# ATmega128RFA1-DevBoard.net
KiCad netlist of a schematic drawn in EAGLE
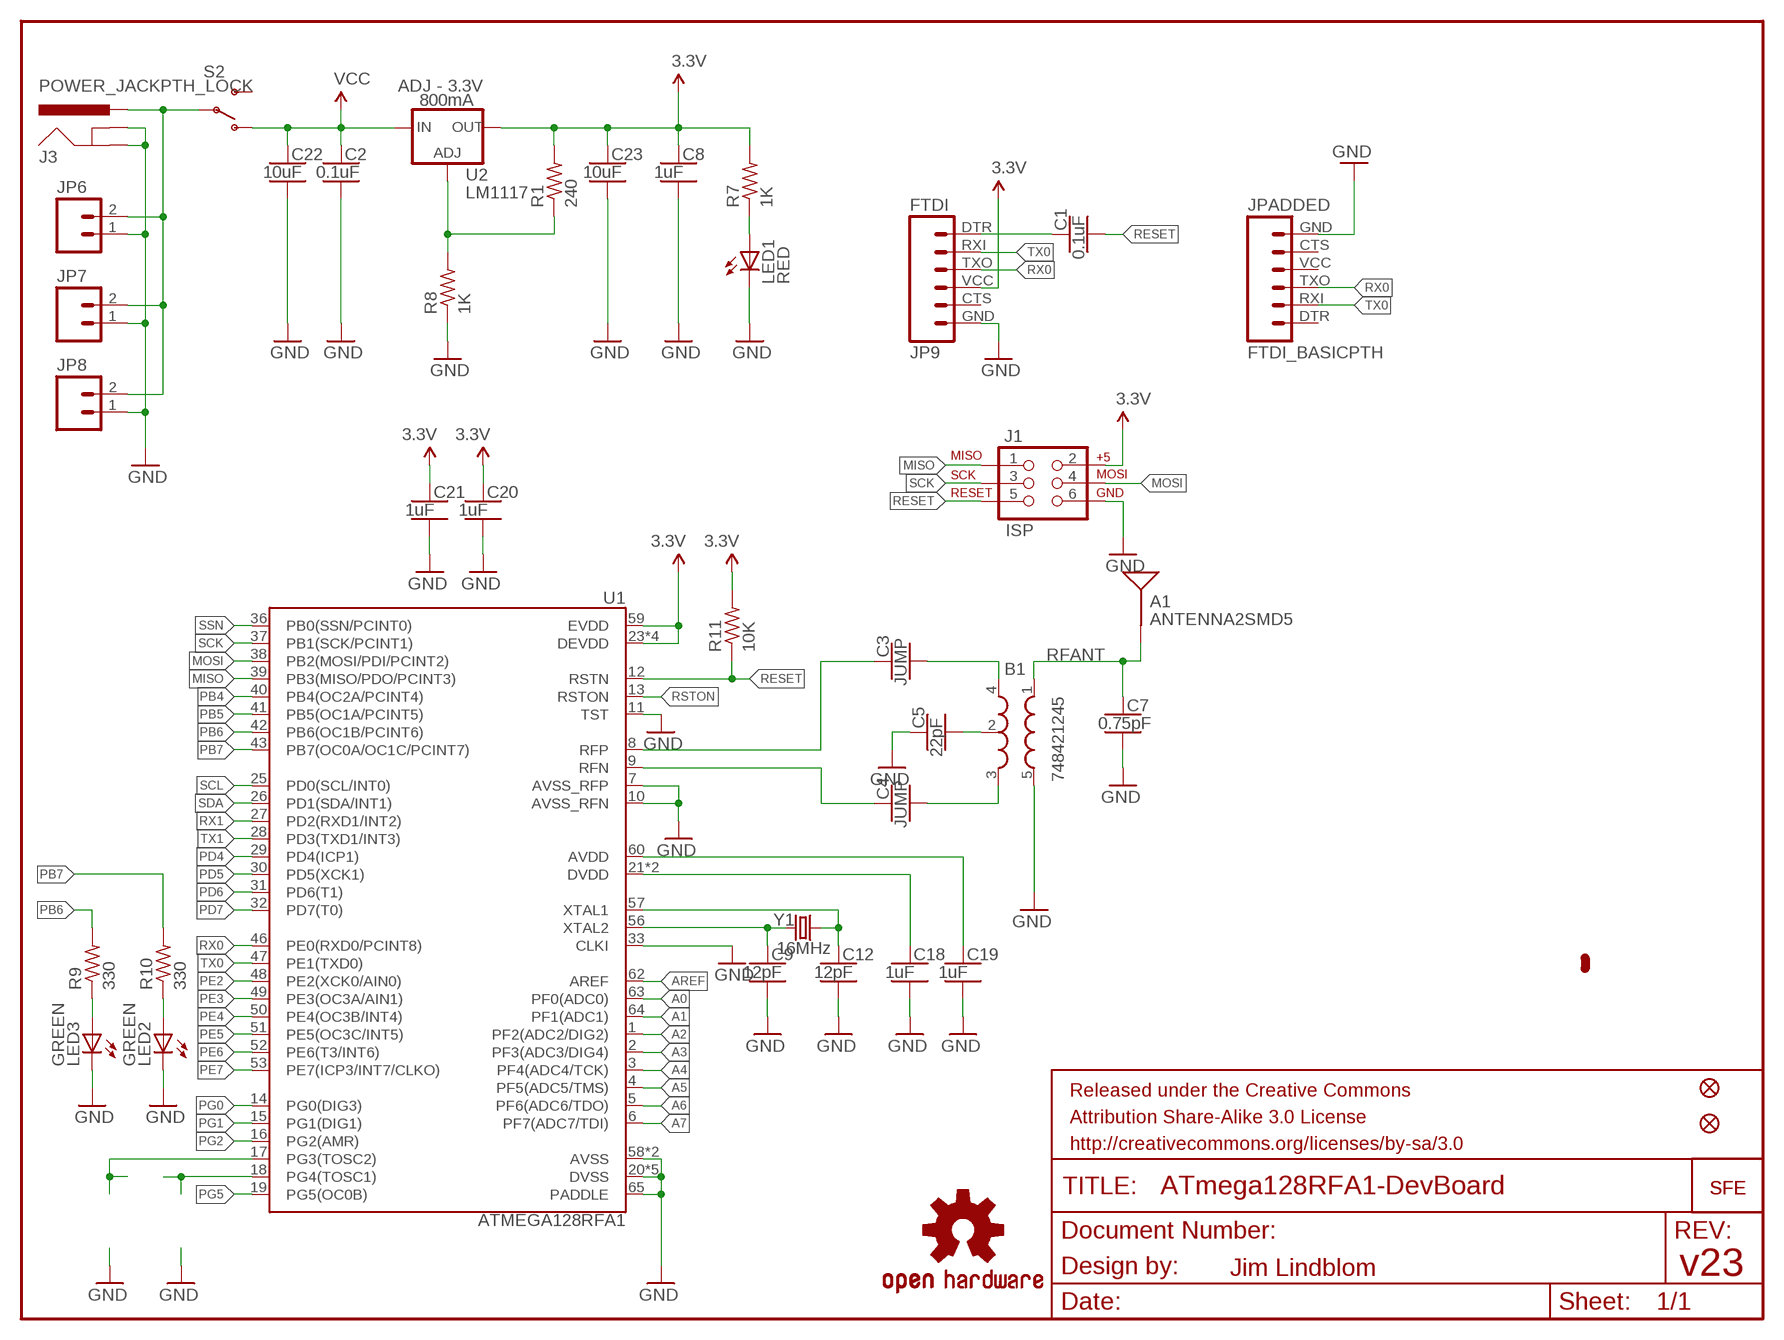
[diagram p0: schematic, sheet 1]

(export (version "E")
  (design (tool "Eeschema 10.0.6"))
  (components
    (comp (ref "A1")
      (value "ANTENNA2SMD5")
      (footprint "eagle-import:ANTENNA-CHIP5")
      (libsource (lib "eagle-import") (part "ANTENNA2SMD5"))
    )
    (comp (ref "B1")
      (value "748421245")
      (footprint "eagle-import:BALUN")
      (libsource (lib "eagle-import") (part "BALUN0805"))
    )
    (comp (ref "C1")
      (value "0.1uF")
      (footprint "eagle-import:CAPC2012X140_HS")
      (fields
        (field (name "MFR") "Murata Electronics North America")
        (field (name "MPN") "GRM21BR71H104KA01L")
      )
      (libsource (lib "eagle-import") (part "CAPACITOR-NP_SMD-2012-0805_CERAMIC-0.1UF"))
    )
    (comp (ref "C2")
      (value "0.1uF")
      (footprint "eagle-import:CAPC2012X140_HS")
      (fields
        (field (name "MFR") "Murata Electronics North America")
        (field (name "MPN") "GRM21BR71H104KA01L")
      )
      (libsource (lib "eagle-import") (part "CAPACITOR-NP_SMD-2012-0805_CERAMIC-0.1UF"))
    )
    (comp (ref "C3")
      (value "JUMP")
      (footprint "eagle-import:CAPC2012X140_HS")
      (libsource (lib "eagle-import") (part "CAPACITOR-NP_SMD-2012-0805_CERAMIC"))
    )
    (comp (ref "C4")
      (value "JUMP")
      (footprint "eagle-import:CAPC2012X140_HS")
      (libsource (lib "eagle-import") (part "CAPACITOR-NP_SMD-2012-0805_CERAMIC"))
    )
    (comp (ref "C5")
      (value "22pF")
      (footprint "eagle-import:CAPC2012X140_HS")
      (fields
        (field (name "MFR") "Murata Electronics North America")
        (field (name "MPN") "GRM21A5C2E220JW01D")
      )
      (libsource (lib "eagle-import") (part "CAPACITOR-NP_SMD-2012-0805_CERAMIC-22PF"))
    )
    (comp (ref "C7")
      (value "0.75pF")
      (footprint "eagle-import:CAPC2012X140_HS")
      (fields
        (field (name "MFR") "Murata Electronics North America")
        (field (name "MPN") "GQM2195C2AR75CB01D")
      )
      (libsource (lib "eagle-import") (part "CAPACITOR-NP_SMD-2012-0805_CERAMIC-0.75PF"))
    )
    (comp (ref "C8")
      (value "1uF")
      (footprint "eagle-import:CAPC2012X140_HS")
      (fields
        (field (name "MFR") "Murata Electronics North America")
        (field (name "MPN") "GRM21BR71H105KA12L")
      )
      (libsource (lib "eagle-import") (part "CAPACITOR-NP_SMD-2012-0805_CERAMIC-1UF"))
    )
    (comp (ref "C9")
      (value "12pF")
      (footprint "eagle-import:CAPC2012X140_HS")
      (fields
        (field (name "MFR") "Murata Electronics North America")
        (field (name "MPN") "GRM21A5C2E120JW01D")
      )
      (libsource (lib "eagle-import") (part "CAPACITOR-NP_SMD-2012-0805_CERAMIC-12PF"))
    )
    (comp (ref "C12")
      (value "12pF")
      (footprint "eagle-import:CAPC2012X140_HS")
      (fields
        (field (name "MFR") "Murata Electronics North America")
        (field (name "MPN") "GRM21A5C2E120JW01D")
      )
      (libsource (lib "eagle-import") (part "CAPACITOR-NP_SMD-2012-0805_CERAMIC-12PF"))
    )
    (comp (ref "C18")
      (value "1uF")
      (footprint "eagle-import:CAPC2012X140_HS")
      (fields
        (field (name "MFR") "Murata Electronics North America")
        (field (name "MPN") "GRM21BR71H105KA12L")
      )
      (libsource (lib "eagle-import") (part "CAPACITOR-NP_SMD-2012-0805_CERAMIC-1UF"))
    )
    (comp (ref "C19")
      (value "1uF")
      (footprint "eagle-import:CAPC2012X140_HS")
      (fields
        (field (name "MFR") "Murata Electronics North America")
        (field (name "MPN") "GRM21BR71H105KA12L")
      )
      (libsource (lib "eagle-import") (part "CAPACITOR-NP_SMD-2012-0805_CERAMIC-1UF"))
    )
    (comp (ref "C20")
      (value "1uF")
      (footprint "eagle-import:CAPC2012X140_HS")
      (fields
        (field (name "MFR") "Murata Electronics North America")
        (field (name "MPN") "GRM21BR71H105KA12L")
      )
      (libsource (lib "eagle-import") (part "CAPACITOR-NP_SMD-2012-0805_CERAMIC-1UF"))
    )
    (comp (ref "C21")
      (value "1uF")
      (footprint "eagle-import:CAPC2012X140_HS")
      (fields
        (field (name "MFR") "Murata Electronics North America")
        (field (name "MPN") "GRM21BR71H105KA12L")
      )
      (libsource (lib "eagle-import") (part "CAPACITOR-NP_SMD-2012-0805_CERAMIC-1UF"))
    )
    (comp (ref "C22")
      (value "10uF")
      (footprint "eagle-import:CAPC2012X140_HS")
      (fields
        (field (name "MFR") "Murata Electronics North America")
        (field (name "MPN") "GRM21BR61E106KA73L")
      )
      (libsource (lib "eagle-import") (part "CAPACITOR-NP_SMD-2012-0805_CERAMIC-10UF"))
    )
    (comp (ref "C23")
      (value "10uF")
      (footprint "eagle-import:CAPC2012X140_HS")
      (fields
        (field (name "MFR") "Murata Electronics North America")
        (field (name "MPN") "GRM21BR61E106KA73L")
      )
      (libsource (lib "eagle-import") (part "CAPACITOR-NP_SMD-2012-0805_CERAMIC-10UF"))
    )
    (comp (ref "FID1")
      (value "FIDUCIALUFIDUCIAL")
      (footprint "eagle-import:MICRO-FIDUCIAL")
      (libsource (lib "eagle-import") (part "FIDUCIALUFIDUCIAL"))
    )
    (comp (ref "FID2")
      (value "FIDUCIALUFIDUCIAL")
      (footprint "eagle-import:MICRO-FIDUCIAL")
      (libsource (lib "eagle-import") (part "FIDUCIALUFIDUCIAL"))
    )
    (comp (ref "J1")
      (value "ISP")
      (footprint "eagle-import:2X3-NS")
      (libsource (lib "eagle-import") (part "AVR_SPI_PRG_6NS"))
    )
    (comp (ref "J3")
      (value "POWER_JACKPTH_LOCK")
      (footprint "eagle-import:POWER_JACK_PTH_LOCK")
      (libsource (lib "eagle-import") (part "POWER_JACKPTH_LOCK"))
    )
    (comp (ref "JP4")
      (value "LOGO-SFENEW")
      (footprint "eagle-import:SFE-NEW-WEBLOGO")
      (libsource (lib "eagle-import") (part "LOGO-SFENEW"))
    )
    (comp (ref "JP6")
      (value "M02JST-PTH-2")
      (footprint "eagle-import:JST-2-PTH")
      (libsource (lib "eagle-import") (part "M02JST-PTH-2"))
    )
    (comp (ref "JP7")
      (value "M021X02_NO_SILK")
      (footprint "eagle-import:1X02_NO_SILK")
      (libsource (lib "eagle-import") (part "M021X02_NO_SILK"))
    )
    (comp (ref "JP8")
      (value "M023.5MM-NO_SILK")
      (footprint "eagle-import:SCREWTERMINAL-3.5MM-2-NS")
      (libsource (lib "eagle-import") (part "M023.5MM-NO_SILK"))
    )
    (comp (ref "JP9")
      (value "FTDI")
      (footprint "eagle-import:FTDI_BASIC")
      (libsource (lib "eagle-import") (part "FTDI_BASICPTH"))
    )
    (comp (ref "JP10")
      (value "LOGO-SFENEW")
      (footprint "eagle-import:SFE-NEW-WEBLOGO")
      (libsource (lib "eagle-import") (part "LOGO-SFENEW"))
    )
    (comp (ref "JPADDED")
      (value "FTDI_BASICPTH")
      (footprint "eagle-import:FTDI_BASIC")
      (fields (field (name "MFR") "Amphenol FCI") (field (name "MPN") "68016-406HLF"))
      (libsource (lib "eagle-import") (part "quadparts_prebuilt_FTDI_BASICPTH"))
    )
    (comp (ref "LED1")
      (value "RED")
      (footprint "eagle-import:LED-0603")
      (libsource (lib "eagle-import") (part "LED0603"))
    )
    (comp (ref "LED2")
      (value "GREEN")
      (footprint "eagle-import:LED-0603")
      (libsource (lib "eagle-import") (part "LED0603"))
    )
    (comp (ref "LED3")
      (value "GREEN")
      (footprint "eagle-import:LED-0603")
      (libsource (lib "eagle-import") (part "LED0603"))
    )
    (comp (ref "R1")
      (value "240")
      (footprint "eagle-import:RESC2012X60_HS")
      (libsource (lib "eagle-import") (part "RESISTOR_SMD-2012-0805"))
    )
    (comp (ref "R7")
      (value "1K")
      (footprint "eagle-import:RESC2012X60_HS")
      (libsource (lib "eagle-import") (part "RESISTOR_SMD-2012-0805"))
    )
    (comp (ref "R8")
      (value "1K")
      (footprint "eagle-import:RESC2012X60_HS")
      (libsource (lib "eagle-import") (part "RESISTOR_SMD-2012-0805"))
    )
    (comp (ref "R9")
      (value "330")
      (footprint "eagle-import:RESC2012X60_HS")
      (fields (field (name "MFR") "Yageo") (field (name "MPN") "RC0805JR-07330RL"))
      (libsource (lib "eagle-import") (part "RESISTOR_SMD-2012-0805-330"))
    )
    (comp (ref "R10")
      (value "330")
      (footprint "eagle-import:RESC2012X60_HS")
      (fields (field (name "MFR") "Yageo") (field (name "MPN") "RC0805JR-07330RL"))
      (libsource (lib "eagle-import") (part "RESISTOR_SMD-2012-0805-330"))
    )
    (comp (ref "R11")
      (value "10K")
      (footprint "eagle-import:RESC2012X60_HS")
      (fields (field (name "MFR") "Yageo") (field (name "MPN") "RC0805JR-0710KL"))
      (libsource (lib "eagle-import") (part "RESISTOR_SMD-2012-0805-10K"))
    )
    (comp (ref "S2")
      (value "SWITCH-SPST-SMD-A")
      (footprint "eagle-import:SWITCH-SPST-SMD-A")
      (libsource (lib "eagle-import") (part "SWITCH-SPST-SMD-A"))
    )
    (comp (ref "U$1")
      (value "OSHW-LOGOS")
      (footprint "eagle-import:OSHW-LOGO-S")
      (libsource (lib "eagle-import") (part "OSHW-LOGOS"))
    )
    (comp (ref "U1")
      (value "ATMEGA128RFA1")
      (footprint "eagle-import:QFN-64")
      (libsource (lib "eagle-import") (part "ATMEGA128RFA1"))
    )
    (comp (ref "U2")
      (value "LM1117")
      (footprint "eagle-import:SOT223")
      (libsource (lib "eagle-import") (part "V_REG_317SMD"))
    )
    (comp (ref "Y1")
      (value "16MHz")
      (footprint "eagle-import:CRYSTAL-SMD-5X3")
      (libsource (lib "eagle-import") (part "CRYSTAL5X3"))
    )
  )
  (nets
    (net (code "1") (name "/RFANT") (class "Default")
      (node (ref "A1") (pin "FEED") (pinfunction "SIGNAL_FEED") (pintype "bidirectional"))
      (node (ref "B1") (pin "1") (pinfunction "IN_1") (pintype "bidirectional"))
      (node (ref "C7") (pin "1") (pinfunction "1_1") (pintype "passive"))
    )
    (net (code "2") (name "3.3V") (class "Default")
      (node (ref "C20") (pin "1") (pinfunction "1_1") (pintype "passive"))
      (node (ref "C21") (pin "1") (pinfunction "1_1") (pintype "passive"))
      (node (ref "C23") (pin "1") (pinfunction "1_1") (pintype "passive"))
      (node (ref "C8") (pin "1") (pinfunction "1_1") (pintype "passive"))
      (node (ref "J1") (pin "2") (pinfunction "2_2") (pintype "passive"))
      (node (ref "JP9") (pin "VCC") (pinfunction "4_VCC") (pintype "passive"))
      (node (ref "R1") (pin "2") (pinfunction "2_2") (pintype "passive"))
      (node (ref "R11") (pin "2") (pinfunction "2_2") (pintype "passive"))
      (node (ref "R7") (pin "2") (pinfunction "2_2") (pintype "passive"))
      (node (ref "U1") (pin "23") (pinfunction "DEVDD_23") (pintype "bidirectional"))
      (node (ref "U1") (pin "34") (pinfunction "DEVDD_34") (pintype "bidirectional"))
      (node (ref "U1") (pin "44") (pinfunction "DEVDD_44") (pintype "bidirectional"))
      (node (ref "U1") (pin "54") (pinfunction "DEVDD_54") (pintype "bidirectional"))
      (node (ref "U1") (pin "59") (pinfunction "EVDD_59") (pintype "bidirectional"))
      (node (ref "U2") (pin "2") (pinfunction "OUT_2") (pintype "output"))
    )
    (net (code "3") (name "A0") (class "Default")
      (node (ref "U1") (pin "63") (pinfunction "PF0(ADC0)_63") (pintype "bidirectional"))
    )
    (net (code "4") (name "A1") (class "Default")
      (node (ref "U1") (pin "64") (pinfunction "PF1(ADC1)_64") (pintype "bidirectional"))
    )
    (net (code "5") (name "A2") (class "Default")
      (node (ref "U1") (pin "1") (pinfunction "PF2(ADC2/DIG2)_1") (pintype "bidirectional"))
    )
    (net (code "6") (name "A3") (class "Default")
      (node (ref "U1") (pin "2") (pinfunction "PF3(ADC3/DIG4)_2") (pintype "bidirectional"))
    )
    (net (code "7") (name "A4") (class "Default")
      (node (ref "U1") (pin "3") (pinfunction "PF4(ADC4/TCK)_3") (pintype "bidirectional"))
    )
    (net (code "8") (name "A5") (class "Default")
      (node (ref "U1") (pin "4") (pinfunction "PF5(ADC5/TMS)_4") (pintype "bidirectional"))
    )
    (net (code "9") (name "A6") (class "Default")
      (node (ref "U1") (pin "5") (pinfunction "PF6(ADC6/TDO)_5") (pintype "bidirectional"))
    )
    (net (code "10") (name "A7") (class "Default")
      (node (ref "U1") (pin "6") (pinfunction "PF7(ADC7/TDI)_6") (pintype "bidirectional"))
    )
    (net (code "11") (name "AREF") (class "Default")
      (node (ref "U1") (pin "62") (pinfunction "AREF_62") (pintype "bidirectional"))
    )
    (net (code "12") (name "GND") (class "Default")
      (node (ref "B1") (pin "5") (pinfunction "GND_5") (pintype "bidirectional"))
      (node (ref "C12") (pin "2") (pinfunction "2_2") (pintype "passive"))
      (node (ref "C18") (pin "2") (pinfunction "2_2") (pintype "passive"))
      (node (ref "C19") (pin "2") (pinfunction "2_2") (pintype "passive"))
      (node (ref "C2") (pin "2") (pinfunction "2_2") (pintype "passive"))
      (node (ref "C20") (pin "2") (pinfunction "2_2") (pintype "passive"))
      (node (ref "C21") (pin "2") (pinfunction "2_2") (pintype "passive"))
      (node (ref "C22") (pin "2") (pinfunction "2_2") (pintype "passive"))
      (node (ref "C23") (pin "2") (pinfunction "2_2") (pintype "passive"))
      (node (ref "C5") (pin "1") (pinfunction "1_1") (pintype "passive"))
      (node (ref "C7") (pin "2") (pinfunction "2_2") (pintype "passive"))
      (node (ref "C8") (pin "2") (pinfunction "2_2") (pintype "passive"))
      (node (ref "C9") (pin "2") (pinfunction "2_2") (pintype "passive"))
      (node (ref "J1") (pin "6") (pinfunction "6_6") (pintype "passive"))
      (node (ref "J3") (pin "GND") (pinfunction "GND_GND") (pintype "bidirectional"))
      (node (ref "J3") (pin "GNDBREAK") (pinfunction "GNDBREAK_GNDBREAK") (pintype "bidirectional"))
      (node (ref "JP6") (pin "1") (pinfunction "1_1") (pintype "passive"))
      (node (ref "JP7") (pin "1") (pinfunction "1_1") (pintype "passive"))
      (node (ref "JP8") (pin "1") (pinfunction "1_1") (pintype "passive"))
      (node (ref "JP9") (pin "GND") (pinfunction "6_GND") (pintype "passive"))
      (node (ref "JPADDED") (pin "GND") (pinfunction "6_GND") (pintype "passive"))
      (node (ref "LED1") (pin "C") (pinfunction "C_C") (pintype "passive"))
      (node (ref "LED2") (pin "C") (pinfunction "C_C") (pintype "passive"))
      (node (ref "LED3") (pin "C") (pinfunction "C_C") (pintype "passive"))
      (node (ref "R8") (pin "1") (pinfunction "1_1") (pintype "passive"))
      (node (ref "U1") (pin "10") (pinfunction "AVSS_RFN_10") (pintype "bidirectional"))
      (node (ref "U1") (pin "11") (pinfunction "TST_11") (pintype "bidirectional"))
      (node (ref "U1") (pin "20") (pinfunction "DVSS_20") (pintype "bidirectional"))
      (node (ref "U1") (pin "24") (pinfunction "DVSS_24") (pintype "bidirectional"))
      (node (ref "U1") (pin "33") (pinfunction "CLKI_33") (pintype "bidirectional"))
      (node (ref "U1") (pin "35") (pinfunction "DVSS_35") (pintype "bidirectional"))
      (node (ref "U1") (pin "45") (pinfunction "DVSS_45") (pintype "bidirectional"))
      (node (ref "U1") (pin "55") (pinfunction "DVSS_55") (pintype "bidirectional"))
      (node (ref "U1") (pin "58") (pinfunction "AVSS_58") (pintype "bidirectional"))
      (node (ref "U1") (pin "61") (pinfunction "AVSS_61") (pintype "bidirectional"))
      (node (ref "U1") (pin "65") (pinfunction "PADDLE_65") (pintype "bidirectional"))
      (node (ref "U1") (pin "7") (pinfunction "AVSS_RFP_7") (pintype "bidirectional"))
    )
    (net (code "13") (name "MISO") (class "Default")
      (node (ref "J1") (pin "1") (pinfunction "1_1") (pintype "passive"))
      (node (ref "U1") (pin "39") (pinfunction "PB3(MISO/PDO/PCINT3)_39") (pintype "bidirectional"))
    )
    (net (code "14") (name "MOSI") (class "Default")
      (node (ref "J1") (pin "4") (pinfunction "4_4") (pintype "passive"))
      (node (ref "U1") (pin "38") (pinfunction "PB2(MOSI/PDI/PCINT2)_38") (pintype "bidirectional"))
    )
    (net (code "15") (name "Net-(B1-GND-Pad2)") (class "Default")
      (node (ref "B1") (pin "2") (pinfunction "GND_2") (pintype "bidirectional"))
      (node (ref "C5") (pin "2") (pinfunction "2_2") (pintype "passive"))
    )
    (net (code "16") (name "Net-(B1-OUT1)") (class "Default")
      (node (ref "B1") (pin "4") (pinfunction "OUT1_4") (pintype "bidirectional"))
      (node (ref "C3") (pin "2") (pinfunction "2_2") (pintype "passive"))
    )
    (net (code "17") (name "Net-(B1-OUT2)") (class "Default")
      (node (ref "B1") (pin "3") (pinfunction "OUT2_3") (pintype "bidirectional"))
      (node (ref "C4") (pin "2") (pinfunction "2_2") (pintype "passive"))
    )
    (net (code "18") (name "Net-(C18-Pad1)") (class "Default")
      (node (ref "C18") (pin "1") (pinfunction "1_1") (pintype "passive"))
      (node (ref "U1") (pin "21") (pinfunction "DVDD_21") (pintype "bidirectional"))
      (node (ref "U1") (pin "22") (pinfunction "DVDD_22") (pintype "bidirectional"))
    )
    (net (code "19") (name "Net-(JP9-1)") (class "Default")
      (node (ref "C1") (pin "1") (pinfunction "1_1") (pintype "passive"))
      (node (ref "JP9") (pin "DTR") (pinfunction "1_DTR") (pintype "passive"))
    )
    (net (code "20") (name "Net-(LED1-PadA)") (class "Default")
      (node (ref "LED1") (pin "A") (pinfunction "A_A") (pintype "passive"))
      (node (ref "R7") (pin "1") (pinfunction "1_1") (pintype "passive"))
    )
    (net (code "21") (name "Net-(LED2-PadA)") (class "Default")
      (node (ref "LED2") (pin "A") (pinfunction "A_A") (pintype "passive"))
      (node (ref "R10") (pin "1") (pinfunction "1_1") (pintype "passive"))
    )
    (net (code "22") (name "Net-(LED3-PadA)") (class "Default")
      (node (ref "LED3") (pin "A") (pinfunction "A_A") (pintype "passive"))
      (node (ref "R9") (pin "1") (pinfunction "1_1") (pintype "passive"))
    )
    (net (code "23") (name "Net-(S2-P)") (class "Default")
      (node (ref "J3") (pin "PWR") (pinfunction "PWR_PWR") (pintype "bidirectional"))
      (node (ref "JP6") (pin "2") (pinfunction "2_2") (pintype "passive"))
      (node (ref "JP7") (pin "2") (pinfunction "2_2") (pintype "passive"))
      (node (ref "JP8") (pin "2") (pinfunction "2_2") (pintype "passive"))
      (node (ref "S2") (pin "2") (pinfunction "P_2") (pintype "passive"))
    )
    (net (code "24") (name "Net-(U1-AVDD)") (class "Default")
      (node (ref "C19") (pin "1") (pinfunction "1_1") (pintype "passive"))
      (node (ref "U1") (pin "60") (pinfunction "AVDD_60") (pintype "bidirectional"))
    )
    (net (code "25") (name "Net-(U1-RFN)") (class "Default")
      (node (ref "C4") (pin "1") (pinfunction "1_1") (pintype "passive"))
      (node (ref "U1") (pin "9") (pinfunction "RFN_9") (pintype "bidirectional"))
    )
    (net (code "26") (name "Net-(U1-RFP)") (class "Default")
      (node (ref "C3") (pin "1") (pinfunction "1_1") (pintype "passive"))
      (node (ref "U1") (pin "8") (pinfunction "RFP_8") (pintype "bidirectional"))
    )
    (net (code "27") (name "Net-(U1-XTAL1)") (class "Default")
      (node (ref "C12") (pin "1") (pinfunction "1_1") (pintype "passive"))
      (node (ref "U1") (pin "57") (pinfunction "XTAL1_57") (pintype "bidirectional"))
      (node (ref "Y1") (pin "3") (pinfunction "2_3") (pintype "passive"))
    )
    (net (code "28") (name "Net-(U1-XTAL2)") (class "Default")
      (node (ref "C9") (pin "1") (pinfunction "1_1") (pintype "passive"))
      (node (ref "U1") (pin "56") (pinfunction "XTAL2_56") (pintype "bidirectional"))
      (node (ref "Y1") (pin "1") (pinfunction "1_1") (pintype "passive"))
    )
    (net (code "29") (name "Net-(U2-ADJ)") (class "Default")
      (node (ref "R1") (pin "1") (pinfunction "1_1") (pintype "passive"))
      (node (ref "R8") (pin "2") (pinfunction "2_2") (pintype "passive"))
      (node (ref "U2") (pin "1") (pinfunction "ADJ_1") (pintype "input"))
    )
    (net (code "30") (name "PB4") (class "Default")
      (node (ref "U1") (pin "40") (pinfunction "PB4(OC2A/PCINT4)_40") (pintype "bidirectional"))
    )
    (net (code "31") (name "PB5") (class "Default")
      (node (ref "U1") (pin "41") (pinfunction "PB5(OC1A/PCINT5)_41") (pintype "bidirectional"))
    )
    (net (code "32") (name "PB6") (class "Default")
      (node (ref "R9") (pin "2") (pinfunction "2_2") (pintype "passive"))
      (node (ref "U1") (pin "42") (pinfunction "PB6(OC1B/PCINT6)_42") (pintype "bidirectional"))
    )
    (net (code "33") (name "PB7") (class "Default")
      (node (ref "R10") (pin "2") (pinfunction "2_2") (pintype "passive"))
      (node (ref "U1") (pin "43") (pinfunction "PB7(OC0A/OC1C/PCINT7)_43") (pintype "bidirectional"))
    )
    (net (code "34") (name "PD4") (class "Default")
      (node (ref "U1") (pin "29") (pinfunction "PD4(ICP1)_29") (pintype "bidirectional"))
    )
    (net (code "35") (name "PD5") (class "Default")
      (node (ref "U1") (pin "30") (pinfunction "PD5(XCK1)_30") (pintype "bidirectional"))
    )
    (net (code "36") (name "PD6") (class "Default")
      (node (ref "U1") (pin "31") (pinfunction "PD6(T1)_31") (pintype "bidirectional"))
    )
    (net (code "37") (name "PD7") (class "Default")
      (node (ref "U1") (pin "32") (pinfunction "PD7(T0)_32") (pintype "bidirectional"))
    )
    (net (code "38") (name "PE2") (class "Default")
      (node (ref "U1") (pin "48") (pinfunction "PE2(XCK0/AIN0)_48") (pintype "bidirectional"))
    )
    (net (code "39") (name "PE3") (class "Default")
      (node (ref "U1") (pin "49") (pinfunction "PE3(OC3A/AIN1)_49") (pintype "bidirectional"))
    )
    (net (code "40") (name "PE4") (class "Default")
      (node (ref "U1") (pin "50") (pinfunction "PE4(OC3B/INT4)_50") (pintype "bidirectional"))
    )
    (net (code "41") (name "PE5") (class "Default")
      (node (ref "U1") (pin "51") (pinfunction "PE5(OC3C/INT5)_51") (pintype "bidirectional"))
    )
    (net (code "42") (name "PE6") (class "Default")
      (node (ref "U1") (pin "52") (pinfunction "PE6(T3/INT6)_52") (pintype "bidirectional"))
    )
    (net (code "43") (name "PE7") (class "Default")
      (node (ref "U1") (pin "53") (pinfunction "PE7(ICP3/INT7/CLKO)_53") (pintype "bidirectional"))
    )
    (net (code "44") (name "PG0") (class "Default")
      (node (ref "U1") (pin "14") (pinfunction "PG0(DIG3)_14") (pintype "bidirectional"))
    )
    (net (code "45") (name "PG1") (class "Default")
      (node (ref "U1") (pin "15") (pinfunction "PG1(DIG1)_15") (pintype "bidirectional"))
    )
    (net (code "46") (name "PG2") (class "Default")
      (node (ref "U1") (pin "16") (pinfunction "PG2(AMR)_16") (pintype "bidirectional"))
    )
    (net (code "47") (name "PG5") (class "Default")
      (node (ref "U1") (pin "19") (pinfunction "PG5(OC0B)_19") (pintype "bidirectional"))
    )
    (net (code "48") (name "RESET") (class "Default")
      (node (ref "C1") (pin "2") (pinfunction "2_2") (pintype "passive"))
      (node (ref "J1") (pin "5") (pinfunction "5_5") (pintype "passive"))
      (node (ref "R11") (pin "1") (pinfunction "1_1") (pintype "passive"))
      (node (ref "U1") (pin "12") (pinfunction "RSTN_12") (pintype "bidirectional"))
    )
    (net (code "49") (name "RSTON") (class "Default")
      (node (ref "U1") (pin "13") (pinfunction "RSTON_13") (pintype "bidirectional"))
    )
    (net (code "50") (name "RX0") (class "Default")
      (node (ref "JP9") (pin "TXO") (pinfunction "3_TXO") (pintype "passive"))
      (node (ref "U1") (pin "46") (pinfunction "PE0(RXD0/PCINT8)_46") (pintype "bidirectional"))
    )
    (net (code "51") (name "RX1") (class "Default")
      (node (ref "U1") (pin "27") (pinfunction "PD2(RXD1/INT2)_27") (pintype "bidirectional"))
    )
    (net (code "52") (name "SCK") (class "Default")
      (node (ref "J1") (pin "3") (pinfunction "3_3") (pintype "passive"))
      (node (ref "U1") (pin "37") (pinfunction "PB1(SCK/PCINT1)_37") (pintype "bidirectional"))
    )
    (net (code "53") (name "SCL") (class "Default")
      (node (ref "U1") (pin "25") (pinfunction "PD0(SCL/INT0)_25") (pintype "bidirectional"))
    )
    (net (code "54") (name "SDA") (class "Default")
      (node (ref "U1") (pin "26") (pinfunction "PD1(SDA/INT1)_26") (pintype "bidirectional"))
    )
    (net (code "55") (name "SSN") (class "Default")
      (node (ref "U1") (pin "36") (pinfunction "PB0(SSN/PCINT0)_36") (pintype "bidirectional"))
    )
    (net (code "56") (name "TX0") (class "Default")
      (node (ref "JP9") (pin "RXI") (pinfunction "2_RXI") (pintype "passive"))
      (node (ref "U1") (pin "47") (pinfunction "PE1(TXD0)_47") (pintype "bidirectional"))
    )
    (net (code "57") (name "TX1") (class "Default")
      (node (ref "U1") (pin "28") (pinfunction "PD3(TXD1/INT3)_28") (pintype "bidirectional"))
    )
    (net (code "58") (name "VCC") (class "Default")
      (node (ref "C2") (pin "1") (pinfunction "1_1") (pintype "passive"))
      (node (ref "C22") (pin "1") (pinfunction "1_1") (pintype "passive"))
      (node (ref "S2") (pin "1") (pinfunction "O_1") (pintype "passive"))
      (node (ref "U2") (pin "3") (pinfunction "IN_3") (pintype "input"))
    )
    (net (code "59") (name "unconnected-(JP9-5-PadCTS)") (class "Default")
      (node (ref "JP9") (pin "CTS") (pinfunction "5_CTS") (pintype "passive"))
    )
    (net (code "60") (name "unconnected-(JPADDED-1-PadDTR)") (class "Default")
      (node (ref "JPADDED") (pin "DTR") (pinfunction "1_DTR") (pintype "passive"))
    )
    (net (code "61") (name "unconnected-(JPADDED-2-PadRXI)") (class "Default")
      (node (ref "JPADDED") (pin "RXI") (pinfunction "2_RXI") (pintype "passive"))
    )
    (net (code "62") (name "unconnected-(JPADDED-3-PadTXO)") (class "Default")
      (node (ref "JPADDED") (pin "TXO") (pinfunction "3_TXO") (pintype "passive"))
    )
    (net (code "63") (name "unconnected-(JPADDED-4-PadVCC)") (class "Default")
      (node (ref "JPADDED") (pin "VCC") (pinfunction "4_VCC") (pintype "passive"))
    )
    (net (code "64") (name "unconnected-(JPADDED-5-PadCTS)") (class "Default")
      (node (ref "JPADDED") (pin "CTS") (pinfunction "5_CTS") (pintype "passive"))
    )
    (net (code "65") (name "unconnected-(S2-S-Pad3)") (class "Default")
      (node (ref "S2") (pin "3") (pinfunction "S_3") (pintype "passive"))
    )
    (net (code "66") (name "unconnected-(U1-PG3(TOSC2)-Pad17)") (class "Default")
      (node (ref "U1") (pin "17") (pinfunction "PG3(TOSC2)_17") (pintype "bidirectional"))
    )
    (net (code "67") (name "unconnected-(U1-PG4(TOSC1)-Pad18)") (class "Default")
      (node (ref "U1") (pin "18") (pinfunction "PG4(TOSC1)_18") (pintype "bidirectional"))
    )
  )
)
